# POMORODO_Timer.net
KiCad netlist of a schematic drawn in EAGLE
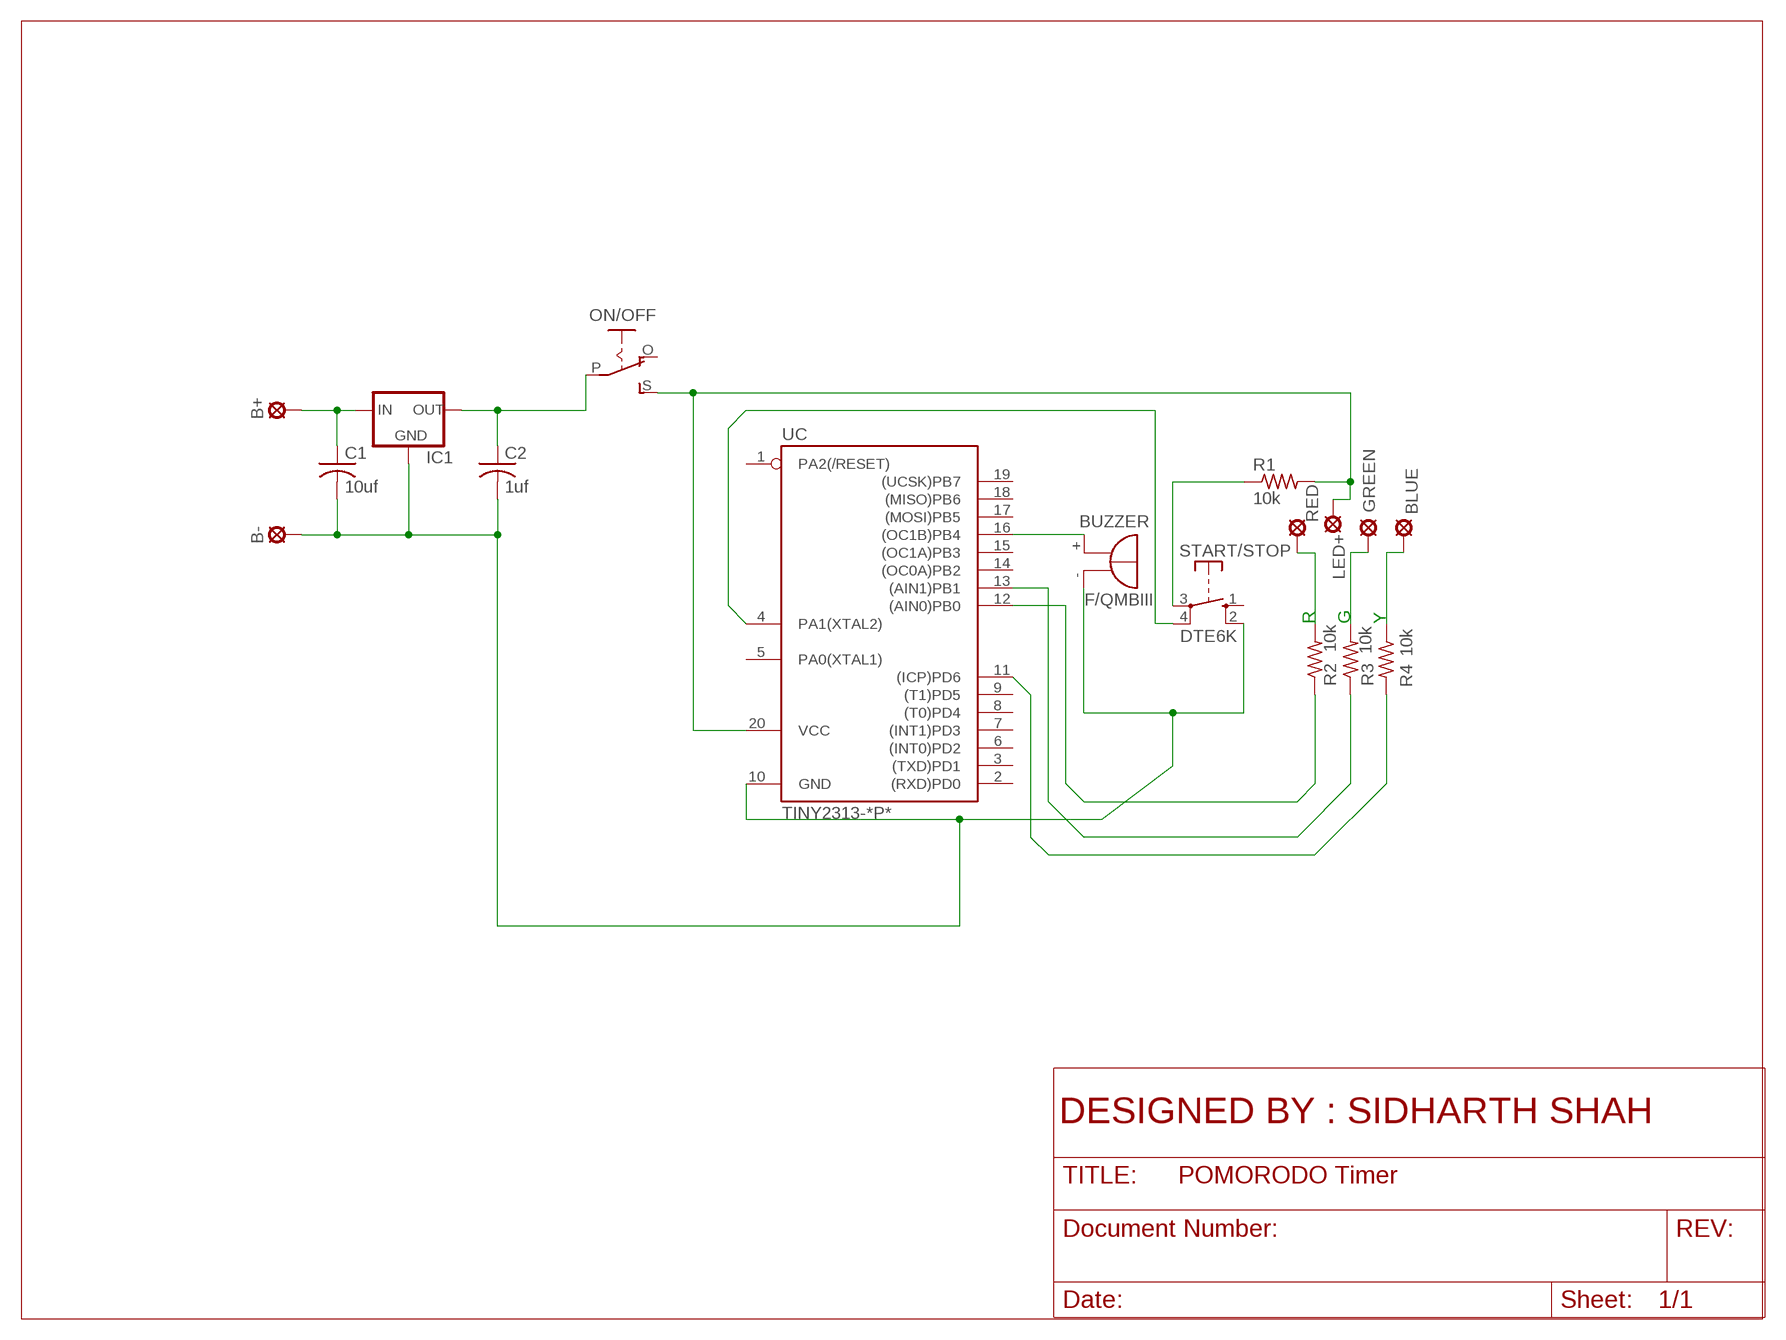
[diagram p0: schematic, sheet 1]

(export (version "E")
  (design (tool "Eeschema 10.0.6"))
  (components
    (comp (ref "B+")
      (value "SE14")
      (footprint "eagle-import:SE14")
      (libsource (lib "eagle-import") (part "SE14"))
    )
    (comp (ref "B-")
      (value "SE14")
      (footprint "eagle-import:SE14")
      (libsource (lib "eagle-import") (part "SE14"))
    )
    (comp (ref "BLUE")
      (value "SE14")
      (footprint "eagle-import:SE14")
      (libsource (lib "eagle-import") (part "SE14"))
    )
    (comp (ref "BUZZER")
      (value "F/QMBIII")
      (footprint "eagle-import:F_QMBIII")
      (libsource (lib "eagle-import") (part "F/QMBIII"))
    )
    (comp (ref "C1")
      (value "10uf")
      (footprint "eagle-import:C025-025X050")
      (libsource (lib "eagle-import") (part "C-US025-025X050"))
    )
    (comp (ref "C2")
      (value "1uf")
      (footprint "eagle-import:C025-025X050")
      (libsource (lib "eagle-import") (part "C-US025-025X050"))
    )
    (comp (ref "GREEN")
      (value "SE14")
      (footprint "eagle-import:SE14")
      (libsource (lib "eagle-import") (part "SE14"))
    )
    (comp (ref "IC1")
      (value "7805")
      (footprint "eagle-import:TO220LV")
      (libsource (lib "eagle-import") (part "7805"))
    )
    (comp (ref "LED+")
      (value "SE14")
      (footprint "eagle-import:SE14")
      (libsource (lib "eagle-import") (part "SE14"))
    )
    (comp (ref "ON/OFF")
      (value "EG1218S")
      (footprint "eagle-import:EG1218")
      (libsource (lib "eagle-import") (part "EG1218S"))
    )
    (comp (ref "R1")
      (value "10k")
      (footprint "eagle-import:0207_10")
      (libsource (lib "eagle-import") (part "R-US_0207/10"))
    )
    (comp (ref "R2")
      (value "10k")
      (footprint "eagle-import:0207_10")
      (libsource (lib "eagle-import") (part "R-US_0207/10"))
    )
    (comp (ref "R3")
      (value "10k")
      (footprint "eagle-import:0207_10")
      (libsource (lib "eagle-import") (part "R-US_0207/10"))
    )
    (comp (ref "R4")
      (value "10k")
      (footprint "eagle-import:0207_10")
      (libsource (lib "eagle-import") (part "R-US_0207/10"))
    )
    (comp (ref "RED")
      (value "SE14")
      (footprint "eagle-import:SE14")
      (libsource (lib "eagle-import") (part "SE14"))
    )
    (comp (ref "START/STOP")
      (value "DTE6K")
      (footprint "eagle-import:DTE6K")
      (libsource (lib "eagle-import") (part "DTE6K"))
    )
    (comp (ref "UC")
      (value "TINY2313-*P*")
      (footprint "eagle-import:DIL20")
      (libsource (lib "eagle-import") (part "TINY2313-P"))
    )
  )
  (nets
    (net (code "1") (name "Net-(BLUE-PadMP)") (class "Default")
      (node (ref "BLUE") (pin "MP") (pinfunction "MP_MP") (pintype "passive"))
      (node (ref "R4") (pin "1") (pinfunction "1_1") (pintype "passive"))
    )
    (net (code "2") (name "Net-(BUZZER-+)") (class "Default")
      (node (ref "B-") (pin "MP") (pinfunction "MP_MP") (pintype "passive"))
      (node (ref "BUZZER") (pin "-") (pinfunction "+_-") (pintype "passive"))
      (node (ref "C1") (pin "2") (pinfunction "2_2") (pintype "passive"))
      (node (ref "C2") (pin "2") (pinfunction "2_2") (pintype "passive"))
      (node (ref "IC1") (pin "2") (pinfunction "GND_2") (pintype "power_in"))
      (node (ref "START/STOP") (pin "2") (pinfunction "S_2") (pintype "passive"))
      (node (ref "UC") (pin "10") (pinfunction "GND_10") (pintype "power_in"))
    )
    (net (code "3") (name "Net-(BUZZER--)") (class "Default")
      (node (ref "BUZZER") (pin "+") (pinfunction "-_+") (pintype "passive"))
      (node (ref "UC") (pin "16") (pinfunction "(OC1B)PB4_16") (pintype "bidirectional"))
    )
    (net (code "4") (name "Net-(GREEN-PadMP)") (class "Default")
      (node (ref "GREEN") (pin "MP") (pinfunction "MP_MP") (pintype "passive"))
      (node (ref "R3") (pin "2") (pinfunction "2_2") (pintype "passive"))
    )
    (net (code "5") (name "Net-(IC1-IN)") (class "Default")
      (node (ref "B+") (pin "MP") (pinfunction "MP_MP") (pintype "passive"))
      (node (ref "C1") (pin "1") (pinfunction "1_1") (pintype "passive"))
      (node (ref "IC1") (pin "1") (pinfunction "IN_1") (pintype "power_in"))
    )
    (net (code "6") (name "Net-(IC1-OUT)") (class "Default")
      (node (ref "C2") (pin "1") (pinfunction "1_1") (pintype "passive"))
      (node (ref "IC1") (pin "3") (pinfunction "OUT_3") (pintype "power_in"))
      (node (ref "ON/OFF") (pin "P") (pinfunction "P_P") (pintype "passive"))
    )
    (net (code "7") (name "Net-(R1-Pad1)") (class "Default")
      (node (ref "R1") (pin "1") (pinfunction "1_1") (pintype "passive"))
      (node (ref "START/STOP") (pin "3") (pinfunction "P_3") (pintype "passive"))
    )
    (net (code "8") (name "Net-(R2-Pad2)") (class "Default")
      (node (ref "R2") (pin "2") (pinfunction "2_2") (pintype "passive"))
      (node (ref "RED") (pin "MP") (pinfunction "MP_MP") (pintype "passive"))
    )
    (net (code "9") (name "Net-(UC-(AIN0)PB0)") (class "Default")
      (node (ref "R2") (pin "1") (pinfunction "1_1") (pintype "passive"))
      (node (ref "UC") (pin "12") (pinfunction "(AIN0)PB0_12") (pintype "bidirectional"))
    )
    (net (code "10") (name "Net-(UC-(AIN1)PB1)") (class "Default")
      (node (ref "R3") (pin "1") (pinfunction "1_1") (pintype "passive"))
      (node (ref "UC") (pin "13") (pinfunction "(AIN1)PB1_13") (pintype "bidirectional"))
    )
    (net (code "11") (name "Net-(UC-(ICP)PD6)") (class "Default")
      (node (ref "R4") (pin "2") (pinfunction "2_2") (pintype "passive"))
      (node (ref "UC") (pin "11") (pinfunction "(ICP)PD6_11") (pintype "bidirectional"))
    )
    (net (code "12") (name "Net-(UC-PA1(XTAL2))") (class "Default")
      (node (ref "START/STOP") (pin "4") (pinfunction "P_4") (pintype "passive"))
      (node (ref "UC") (pin "4") (pinfunction "PA1(XTAL2)_4") (pintype "bidirectional"))
    )
    (net (code "13") (name "Net-(UC-VCC)") (class "Default")
      (node (ref "LED+") (pin "MP") (pinfunction "MP_MP") (pintype "passive"))
      (node (ref "ON/OFF") (pin "S") (pinfunction "S_S") (pintype "passive"))
      (node (ref "R1") (pin "2") (pinfunction "2_2") (pintype "passive"))
      (node (ref "UC") (pin "20") (pinfunction "VCC_20") (pintype "power_in"))
    )
    (net (code "14") (name "unconnected-(ON/OFF-PadO)") (class "Default")
      (node (ref "ON/OFF") (pin "O") (pinfunction "O_O") (pintype "passive"))
    )
    (net (code "15") (name "unconnected-(START/STOP-S-Pad1)") (class "Default")
      (node (ref "START/STOP") (pin "1") (pinfunction "S_1") (pintype "passive"))
    )
    (net (code "16") (name "unconnected-(UC-(INT0)PD2-Pad6)") (class "Default")
      (node (ref "UC") (pin "6") (pinfunction "(INT0)PD2_6") (pintype "bidirectional"))
    )
    (net (code "17") (name "unconnected-(UC-(INT1)PD3-Pad7)") (class "Default")
      (node (ref "UC") (pin "7") (pinfunction "(INT1)PD3_7") (pintype "bidirectional"))
    )
    (net (code "18") (name "unconnected-(UC-(MISO)PB6-Pad18)") (class "Default")
      (node (ref "UC") (pin "18") (pinfunction "(MISO)PB6_18") (pintype "bidirectional"))
    )
    (net (code "19") (name "unconnected-(UC-(MOSI)PB5-Pad17)") (class "Default")
      (node (ref "UC") (pin "17") (pinfunction "(MOSI)PB5_17") (pintype "bidirectional"))
    )
    (net (code "20") (name "unconnected-(UC-(OC0A)PB2-Pad14)") (class "Default")
      (node (ref "UC") (pin "14") (pinfunction "(OC0A)PB2_14") (pintype "bidirectional"))
    )
    (net (code "21") (name "unconnected-(UC-(OC1A)PB3-Pad15)") (class "Default")
      (node (ref "UC") (pin "15") (pinfunction "(OC1A)PB3_15") (pintype "bidirectional"))
    )
    (net (code "22") (name "unconnected-(UC-(RXD)PD0-Pad2)") (class "Default")
      (node (ref "UC") (pin "2") (pinfunction "(RXD)PD0_2") (pintype "bidirectional"))
    )
    (net (code "23") (name "unconnected-(UC-(T0)PD4-Pad8)") (class "Default")
      (node (ref "UC") (pin "8") (pinfunction "(T0)PD4_8") (pintype "bidirectional"))
    )
    (net (code "24") (name "unconnected-(UC-(T1)PD5-Pad9)") (class "Default")
      (node (ref "UC") (pin "9") (pinfunction "(T1)PD5_9") (pintype "bidirectional"))
    )
    (net (code "25") (name "unconnected-(UC-(TXD)PD1-Pad3)") (class "Default")
      (node (ref "UC") (pin "3") (pinfunction "(TXD)PD1_3") (pintype "bidirectional"))
    )
    (net (code "26") (name "unconnected-(UC-(UCSK)PB7-Pad19)") (class "Default")
      (node (ref "UC") (pin "19") (pinfunction "(UCSK)PB7_19") (pintype "bidirectional"))
    )
    (net (code "27") (name "unconnected-(UC-PA0(XTAL1)-Pad5)") (class "Default")
      (node (ref "UC") (pin "5") (pinfunction "PA0(XTAL1)_5") (pintype "bidirectional"))
    )
    (net (code "28") (name "unconnected-(UC-PA2({slash}RESET)-Pad1)") (class "Default")
      (node (ref "UC") (pin "1") (pinfunction "PA2(/RESET)_1") (pintype "input"))
    )
  )
)
